# Internet_Of_Everthing.net
KiCad netlist of a schematic drawn in Altium Designer
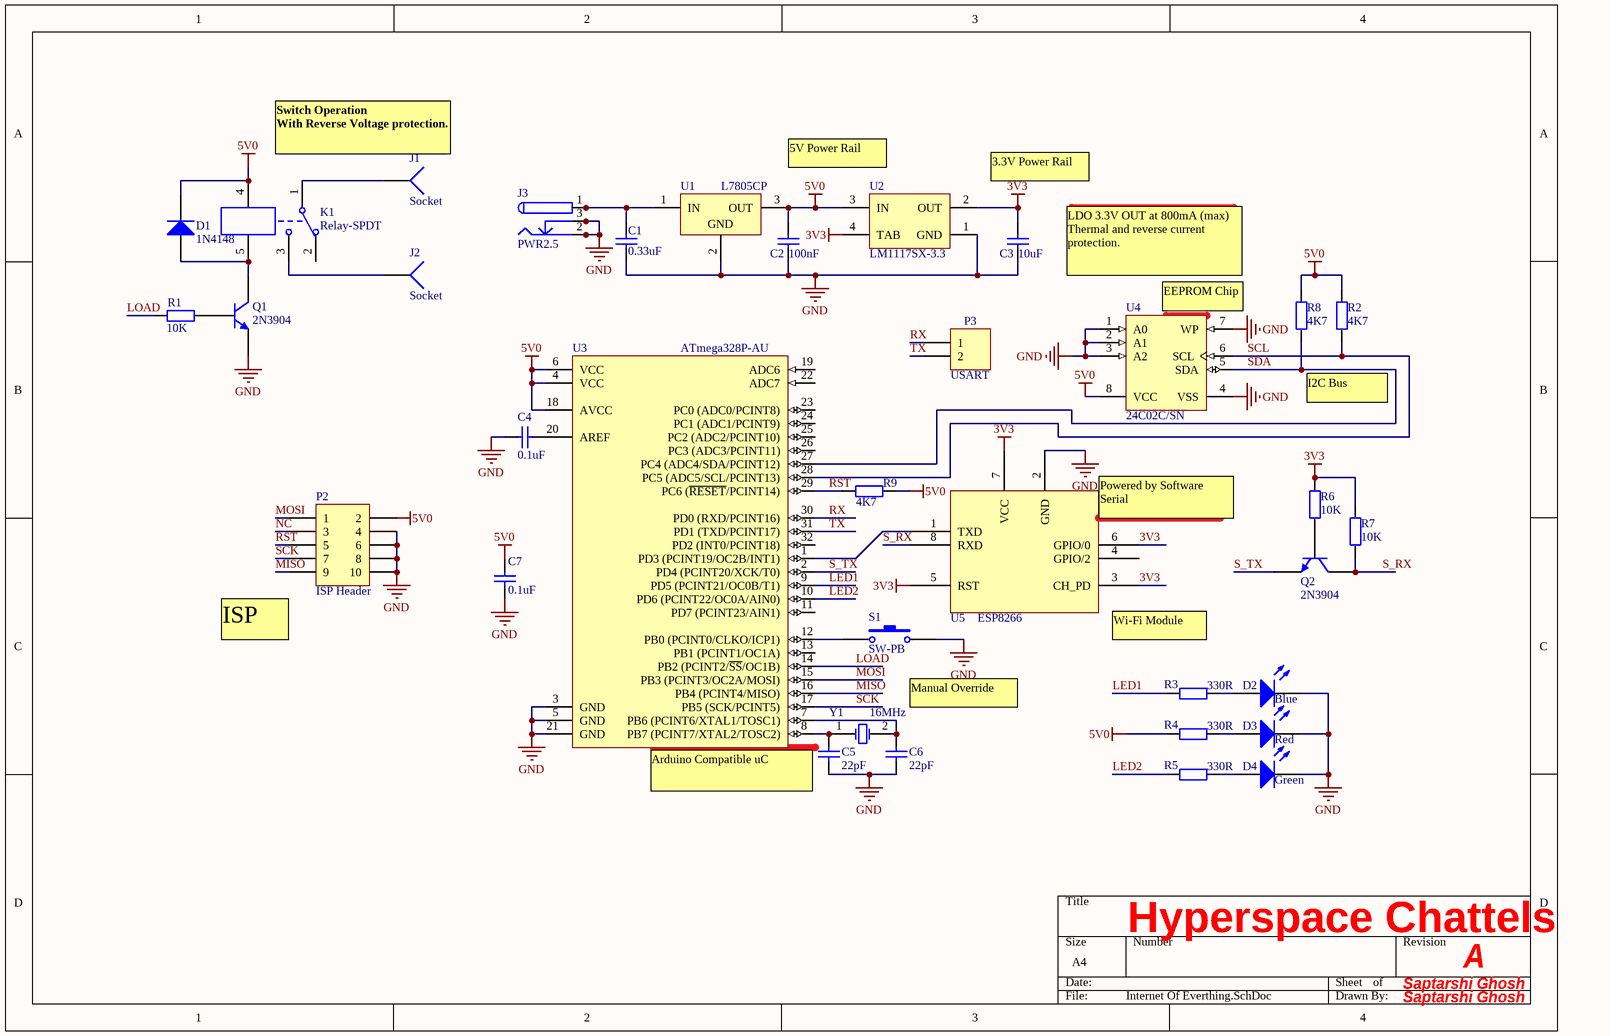
[diagram p0: Internet Of Everthing.SchDoc]

(export (version "E")
  (design (tool "Eeschema 10.0.6"))
  (components
    (comp (ref "C1")
      (value "0.33uF")
      (footprint "6-0805_M")
      (description "Capacitor")
      (fields (field (name "Comment") "Cap") (field (name "PUBLISHER") "Altium Limited"))
      (libsource (lib "Miscellaneous Devices") (part "Cap"))
    )
    (comp (ref "C2")
      (value "100nF")
      (footprint "6-0805_M")
      (description "Capacitor")
      (fields (field (name "Comment") "Cap") (field (name "PUBLISHER") "Altium Limited"))
      (libsource (lib "Miscellaneous Devices") (part "Cap"))
    )
    (comp (ref "C3")
      (value "10uF")
      (footprint "6-0805_M")
      (description "Capacitor")
      (fields (field (name "Comment") "Cap") (field (name "PUBLISHER") "Altium Limited"))
      (libsource (lib "Miscellaneous Devices") (part "Cap"))
    )
    (comp (ref "C4")
      (value "0.1uF")
      (footprint "6-0805_M")
      (description "Capacitor")
      (fields (field (name "Comment") "Cap") (field (name "PUBLISHER") "Altium Limited"))
      (libsource (lib "Miscellaneous Devices") (part "Cap"))
    )
    (comp (ref "C5")
      (value "22pF")
      (footprint "6-0805_M")
      (description "Capacitor")
      (fields (field (name "Comment") "Cap") (field (name "PUBLISHER") "Altium Limited"))
      (libsource (lib "Miscellaneous Devices") (part "Cap"))
    )
    (comp (ref "C6")
      (value "22pF")
      (footprint "6-0805_M")
      (description "Capacitor")
      (fields (field (name "Comment") "Cap") (field (name "PUBLISHER") "Altium Limited"))
      (libsource (lib "Miscellaneous Devices") (part "Cap"))
    )
    (comp (ref "C7")
      (value "0.1uF")
      (footprint "6-0805_M")
      (description "Capacitor")
      (fields (field (name "Comment") "Cap") (field (name "PUBLISHER") "Altium Limited"))
      (libsource (lib "Miscellaneous Devices") (part "Cap"))
    )
    (comp (ref "D1")
      (value "1N4148")
      (footprint "SOD-323")
      (description "High Conductance Fast Diode")
      (fields (field (name "PUBLISHER") "Altium Limited"))
      (libsource (lib "FSC Discrete Diode") (part "1N4148"))
    )
    (comp (ref "D2")
      (value "LED0")
      (footprint "6-0805_M")
      (description "Typical INFRARED GaAs LED")
      (fields (field (name "PUBLISHER") "Altium Limited"))
      (libsource (lib "Miscellaneous Devices") (part "LED0"))
    )
    (comp (ref "D3")
      (value "LED0")
      (footprint "6-0805_M")
      (description "Typical INFRARED GaAs LED")
      (fields (field (name "PUBLISHER") "Altium Limited"))
      (libsource (lib "Miscellaneous Devices") (part "LED0"))
    )
    (comp (ref "D4")
      (value "LED0")
      (footprint "6-0805_M")
      (description "Typical INFRARED GaAs LED")
      (fields (field (name "PUBLISHER") "Altium Limited"))
      (libsource (lib "Miscellaneous Devices") (part "LED0"))
    )
    (comp (ref "J1")
      (value "Socket")
      (footprint "PIN1")
      (fields (field (name "PUBLISHER") "Altium Limited"))
      (libsource (lib "Miscellaneous Connectors") (part "Socket"))
    )
    (comp (ref "J2")
      (value "Socket")
      (footprint "PIN1")
      (fields (field (name "PUBLISHER") "Altium Limited"))
      (libsource (lib "Miscellaneous Connectors") (part "Socket"))
    )
    (comp (ref "J3")
      (value "PWR2.5")
      (footprint "KLD-0202")
      (description "Low Voltage Power Supply Connector")
      (fields (field (name "PUBLISHER") "Altium Limited"))
      (libsource (lib "Miscellaneous Connectors") (part "PWR2.5"))
    )
    (comp (ref "K1")
      (value "Relay-SPDT")
      (footprint "G5LA-141")
      (description "Single-Pole Dual-Throw Relay")
      (fields (field (name "PUBLISHER") "Altium Limited"))
      (libsource (lib "Miscellaneous Devices") (part "Relay-SPDT"))
    )
    (comp (ref "P2")
      (value "ISP Header")
      (footprint "HDR2X5")
      (description "Header, 5-Pin, Dual row")
      (fields (field (name "PUBLISHER") "Altium Limited"))
      (libsource (lib "Miscellaneous Connectors") (part "Header 5X2"))
    )
    (comp (ref "P3")
      (value "USART")
      (footprint "HDR1X2")
      (description "Header, 2-Pin")
      (fields (field (name "PUBLISHER") "Altium Limited"))
      (libsource (lib "Miscellaneous Connectors") (part "Header 2"))
    )
    (comp (ref "Q1")
      (value "2N3904")
      (footprint "SOT-23_M")
      (description "NPN General Purpose Amplifier")
      (fields (field (name "PUBLISHER") "Altium Limited"))
      (libsource (lib "FSC Discrete BJT") (part "2N3904"))
    )
    (comp (ref "Q2")
      (value "2N3904")
      (footprint "SOT-23_M")
      (description "NPN General Purpose Amplifier")
      (fields (field (name "PUBLISHER") "Altium Limited"))
      (libsource (lib "FSC Discrete BJT") (part "2N3904"))
    )
    (comp (ref "R1")
      (value "10K")
      (footprint "6-0805_M")
      (description "Resistor")
      (fields (field (name "Comment") "Res2") (field (name "PUBLISHER") "Altium Limited"))
      (libsource (lib "") (part "Res2_3"))
    )
    (comp (ref "R2")
      (value "4K7")
      (footprint "6-0805_M")
      (description "Resistor")
      (fields (field (name "Comment") "Res2") (field (name "PUBLISHER") "Altium Limited"))
      (libsource (lib "Miscellaneous Devices") (part "Res2"))
    )
    (comp (ref "R3")
      (value "330R")
      (footprint "6-0805_M")
      (description "Resistor")
      (fields (field (name "Comment") "Res2") (field (name "PUBLISHER") "Altium Limited"))
      (libsource (lib "") (part "Res2_2"))
    )
    (comp (ref "R4")
      (value "330R")
      (footprint "6-0805_M")
      (description "Resistor")
      (fields (field (name "Comment") "Res2") (field (name "PUBLISHER") "Altium Limited"))
      (libsource (lib "") (part "Res2_2"))
    )
    (comp (ref "R5")
      (value "330R")
      (footprint "6-0805_M")
      (description "Resistor")
      (fields (field (name "Comment") "Res2") (field (name "PUBLISHER") "Altium Limited"))
      (libsource (lib "") (part "Res2_2"))
    )
    (comp (ref "R6")
      (value "10K")
      (footprint "6-0805_M")
      (description "Resistor")
      (fields (field (name "Comment") "Res2") (field (name "PUBLISHER") "Altium Limited"))
      (libsource (lib "") (part "Res2_1"))
    )
    (comp (ref "R7")
      (value "10K")
      (footprint "6-0805_M")
      (description "Resistor")
      (fields (field (name "Comment") "Res2") (field (name "PUBLISHER") "Altium Limited"))
      (libsource (lib "") (part "Res2_1"))
    )
    (comp (ref "R8")
      (value "4K7")
      (footprint "6-0805_M")
      (description "Resistor")
      (fields (field (name "Comment") "Res2") (field (name "PUBLISHER") "Altium Limited"))
      (libsource (lib "Miscellaneous Devices") (part "Res2"))
    )
    (comp (ref "R9")
      (value "4K7")
      (footprint "6-0805_M")
      (description "Resistor")
      (fields (field (name "Comment") "g") (field (name "PUBLISHER") "Altium Limited"))
      (libsource (lib "") (part "Res2_2"))
    )
    (comp (ref "S1")
      (value "SW-PB")
      (footprint "Tactile Swithc")
      (description "Switch")
      (fields (field (name "PUBLISHER") "Altium Limited"))
      (libsource (lib "Miscellaneous Devices") (part "SW-PB"))
    )
    (comp (ref "U1")
      (value "L7805CP")
      (footprint "SOT223_M")
      (description "Positive Voltage Regulator")
      (fields (field (name "PUBLISHER") "Altium Limited"))
      (libsource (lib "ST Power Mgt Voltage Regulator") (part "L7805CP"))
    )
    (comp (ref "U2")
      (value "LM1117SX-3.3")
      (footprint "SOT223_M")
      (description "800mA Low-Dropout Linear Regulator, 3-pin TO-263")
      (fields
        (field (name "MANUFACTURER") "National Semiconductor")
        (field (name "PUBLISHER") "Altium Limited")
      )
      (libsource (lib "NSC LDO") (part "LM1117SX-3.3"))
    )
    (comp (ref "U3")
      (value "ATmega328P-AU")
      (footprint "32A_M")
      (fields (field (name "PUBLISHER") "Altium Limited"))
      (libsource (lib "Atmel Microcontroller 8-Bit megaAVR") (part "ATmega328P-AU"))
    )
    (comp (ref "U4")
      (value "24C02C/SN")
      (footprint "SOIC-SN8_M")
      (description "2Kbit, 400kHz, 5V, I2C Serial EEPROM, 8-Pin SOIC 150mil, Commercial Temperature")
      (fields (field (name "PUBLISHER") "Altium Limited"))
      (libsource (lib "Microchip Memory I2C Serial EEPROM") (part "24C02C/SN"))
    )
    (comp (ref "U5")
      (value "ESP8266")
      (footprint "HDR2X4")
      (description "Low cost, Wi-Fi module")
      (libsource (lib "MSP430") (part "ESP8266"))
    )
    (comp (ref "Y1")
      (value "16MHz")
      (footprint "RAD-0.2")
      (description "Crystal Oscillator")
      (fields (field (name "PUBLISHER") "Altium Limited"))
      (libsource (lib "Miscellaneous Devices") (part "XTAL"))
    )
  )
  (nets
    (net (code "1") (name "/LED1") (class "Default")
      (node (ref "R3") (pin "2") (pinfunction "2_2") (pintype "passive"))
      (node (ref "U3") (pin "9") (pinfunction "PD5_(PCINT21/OC0B/T1)_9") (pintype "bidirectional"))
    )
    (net (code "2") (name "/LED2") (class "Default")
      (node (ref "R5") (pin "2") (pinfunction "2_2") (pintype "passive"))
      (node (ref "U3") (pin "10") (pinfunction "PD6_(PCINT22/OC0A/AIN0)_10") (pintype "bidirectional"))
    )
    (net (code "3") (name "/LOAD") (class "Default")
      (node (ref "R1") (pin "1") (pinfunction "1_1") (pintype "passive"))
      (node (ref "U3") (pin "14") (pinfunction "PB2_(PCINT2/~{SS}/OC1B)_14") (pintype "bidirectional"))
    )
    (net (code "4") (name "/MISO") (class "Default")
      (node (ref "P2") (pin "9") (pinfunction "9_9") (pintype "passive"))
      (node (ref "U3") (pin "16") (pinfunction "PB4_(PCINT4/MISO)_16") (pintype "bidirectional"))
    )
    (net (code "5") (name "/MOSI") (class "Default")
      (node (ref "P2") (pin "1") (pinfunction "1_1") (pintype "passive"))
      (node (ref "U3") (pin "15") (pinfunction "PB3_(PCINT3/OC2A/MOSI)_15") (pintype "bidirectional"))
    )
    (net (code "6") (name "/NC") (class "Default")
      (node (ref "P2") (pin "3") (pinfunction "3_3") (pintype "passive"))
    )
    (net (code "7") (name "/RST") (class "Default")
      (node (ref "P2") (pin "5") (pinfunction "5_5") (pintype "passive"))
      (node (ref "R9") (pin "2") (pinfunction "2_2") (pintype "passive"))
      (node (ref "U3") (pin "29") (pinfunction "PC6_(~{RESET}/PCINT14)_29") (pintype "bidirectional"))
    )
    (net (code "8") (name "/RX") (class "Default")
      (node (ref "P3") (pin "1") (pinfunction "1_1") (pintype "passive"))
      (node (ref "U3") (pin "30") (pinfunction "PD0_(RXD/PCINT16)_30") (pintype "bidirectional"))
    )
    (net (code "9") (name "/SCK") (class "Default")
      (node (ref "P2") (pin "7") (pinfunction "7_7") (pintype "passive"))
      (node (ref "U3") (pin "17") (pinfunction "PB5_(SCK/PCINT5)_17") (pintype "bidirectional"))
    )
    (net (code "10") (name "/SCL") (class "Default")
      (node (ref "R2") (pin "1") (pinfunction "1_1") (pintype "passive"))
      (node (ref "U3") (pin "28") (pinfunction "PC5_(ADC5/SCL/PCINT13)_28") (pintype "bidirectional"))
      (node (ref "U4") (pin "6") (pinfunction "SCL_6") (pintype "input"))
    )
    (net (code "11") (name "/SDA") (class "Default")
      (node (ref "R8") (pin "1") (pinfunction "1_1") (pintype "passive"))
      (node (ref "U3") (pin "27") (pinfunction "PC4_(ADC4/SDA/PCINT12)_27") (pintype "bidirectional"))
      (node (ref "U4") (pin "5") (pinfunction "SDA_5") (pintype "bidirectional"))
    )
    (net (code "12") (name "/S_RX") (class "Default")
      (node (ref "Q2") (pin "3") (pinfunction "C_3") (pintype "passive"))
      (node (ref "R7") (pin "2") (pinfunction "2_2") (pintype "passive"))
      (node (ref "U5") (pin "8") (pinfunction "RXD_8") (pintype "passive"))
    )
    (net (code "13") (name "/S_TX") (class "Default")
      (node (ref "Q2") (pin "2") (pinfunction "E_2") (pintype "passive"))
      (node (ref "U3") (pin "2") (pinfunction "PD4_(PCINT20/XCK/T0)_2") (pintype "bidirectional"))
    )
    (net (code "14") (name "/TX") (class "Default")
      (node (ref "P3") (pin "2") (pinfunction "2_2") (pintype "passive"))
      (node (ref "U3") (pin "31") (pinfunction "PD1_(TXD/PCINT17)_31") (pintype "bidirectional"))
    )
    (net (code "15") (name "3V3") (class "Default")
      (node (ref "C3") (pin "1") (pinfunction "1_1") (pintype "passive"))
      (node (ref "R6") (pin "1") (pinfunction "1_1") (pintype "passive"))
      (node (ref "R7") (pin "1") (pinfunction "1_1") (pintype "passive"))
      (node (ref "U2") (pin "2") (pinfunction "OUT_2") (pintype "power_in"))
      (node (ref "U2") (pin "4") (pinfunction "TAB_4") (pintype "power_in"))
      (node (ref "U5") (pin "3") (pinfunction "CH_PD_3") (pintype "passive"))
      (node (ref "U5") (pin "5") (pinfunction "RST_5") (pintype "passive"))
      (node (ref "U5") (pin "6") (pinfunction "GPIO/0_6") (pintype "passive"))
      (node (ref "U5") (pin "7") (pinfunction "VCC_7") (pintype "passive"))
    )
    (net (code "16") (name "5V0") (class "Default")
      (node (ref "C2") (pin "1") (pinfunction "1_1") (pintype "passive"))
      (node (ref "C7") (pin "2") (pinfunction "2_2") (pintype "passive"))
      (node (ref "D1") (pin "2") (pinfunction "K_2") (pintype "passive"))
      (node (ref "K1") (pin "4") (pinfunction "4_4") (pintype "passive"))
      (node (ref "P2") (pin "2") (pinfunction "2_2") (pintype "passive"))
      (node (ref "R2") (pin "2") (pinfunction "2_2") (pintype "passive"))
      (node (ref "R4") (pin "2") (pinfunction "2_2") (pintype "passive"))
      (node (ref "R8") (pin "2") (pinfunction "2_2") (pintype "passive"))
      (node (ref "R9") (pin "1") (pinfunction "1_1") (pintype "passive"))
      (node (ref "U1") (pin "3") (pinfunction "OUT_3") (pintype "open_emitter"))
      (node (ref "U2") (pin "3") (pinfunction "IN_3") (pintype "power_in"))
      (node (ref "U3") (pin "18") (pinfunction "AVCC_18") (pintype "power_in"))
      (node (ref "U3") (pin "4") (pinfunction "VCC_4") (pintype "power_in"))
      (node (ref "U3") (pin "6") (pinfunction "VCC_6") (pintype "power_in"))
      (node (ref "U4") (pin "8") (pinfunction "VCC_8") (pintype "power_in"))
    )
    (net (code "17") (name "GND") (class "Default")
      (node (ref "C1") (pin "1") (pinfunction "1_1") (pintype "passive"))
      (node (ref "C2") (pin "2") (pinfunction "2_2") (pintype "passive"))
      (node (ref "C3") (pin "2") (pinfunction "2_2") (pintype "passive"))
      (node (ref "C4") (pin "1") (pinfunction "1_1") (pintype "passive"))
      (node (ref "C5") (pin "2") (pinfunction "2_2") (pintype "passive"))
      (node (ref "C6") (pin "2") (pinfunction "2_2") (pintype "passive"))
      (node (ref "C7") (pin "1") (pinfunction "1_1") (pintype "passive"))
      (node (ref "D2") (pin "2") (pinfunction "K_2") (pintype "passive"))
      (node (ref "D3") (pin "2") (pinfunction "K_2") (pintype "passive"))
      (node (ref "D4") (pin "2") (pinfunction "K_2") (pintype "passive"))
      (node (ref "J3") (pin "2") (pinfunction "2_2") (pintype "power_in"))
      (node (ref "J3") (pin "2A") (pinfunction "2A_2A") (pintype "power_in"))
      (node (ref "J3") (pin "2B") (pinfunction "2B_2B") (pintype "power_in"))
      (node (ref "J3") (pin "3") (pinfunction "3_3") (pintype "power_in"))
      (node (ref "J3") (pin "3A") (pinfunction "3A_3A") (pintype "power_in"))
      (node (ref "J3") (pin "3B") (pinfunction "3B_3B") (pintype "power_in"))
      (node (ref "P2") (pin "10") (pinfunction "10_10") (pintype "passive"))
      (node (ref "P2") (pin "4") (pinfunction "4_4") (pintype "passive"))
      (node (ref "P2") (pin "6") (pinfunction "6_6") (pintype "passive"))
      (node (ref "P2") (pin "8") (pinfunction "8_8") (pintype "passive"))
      (node (ref "Q1") (pin "2") (pinfunction "E_2") (pintype "passive"))
      (node (ref "S1") (pin "2") (pinfunction "2_2") (pintype "passive"))
      (node (ref "U1") (pin "2") (pinfunction "GND_2") (pintype "power_in"))
      (node (ref "U2") (pin "1") (pinfunction "GND_1") (pintype "power_in"))
      (node (ref "U3") (pin "21") (pinfunction "GND_21") (pintype "power_in"))
      (node (ref "U3") (pin "3") (pinfunction "GND_3") (pintype "power_in"))
      (node (ref "U3") (pin "5") (pinfunction "GND_5") (pintype "power_in"))
      (node (ref "U4") (pin "1") (pinfunction "A0_1") (pintype "input"))
      (node (ref "U4") (pin "2") (pinfunction "A1_2") (pintype "input"))
      (node (ref "U4") (pin "3") (pinfunction "A2_3") (pintype "input"))
      (node (ref "U4") (pin "4") (pinfunction "VSS_4") (pintype "power_in"))
      (node (ref "U4") (pin "7") (pinfunction "WP_7") (pintype "input"))
      (node (ref "U5") (pin "2") (pinfunction "GND_2") (pintype "passive"))
    )
    (net (code "18") (name "Net-(D1-A)") (class "Default")
      (node (ref "D1") (pin "1") (pinfunction "A_1") (pintype "passive"))
      (node (ref "K1") (pin "5") (pinfunction "5_5") (pintype "passive"))
      (node (ref "Q1") (pin "3") (pinfunction "C_3") (pintype "passive"))
    )
    (net (code "19") (name "Net-(D2-A)") (class "Default")
      (node (ref "D2") (pin "1") (pinfunction "A_1") (pintype "passive"))
      (node (ref "R3") (pin "1") (pinfunction "1_1") (pintype "passive"))
    )
    (net (code "20") (name "Net-(D3-A)") (class "Default")
      (node (ref "D3") (pin "1") (pinfunction "A_1") (pintype "passive"))
      (node (ref "R4") (pin "1") (pinfunction "1_1") (pintype "passive"))
    )
    (net (code "21") (name "Net-(D4-A)") (class "Default")
      (node (ref "D4") (pin "1") (pinfunction "A_1") (pintype "passive"))
      (node (ref "R5") (pin "1") (pinfunction "1_1") (pintype "passive"))
    )
    (net (code "22") (name "Net-(J1-Pad1)") (class "Default")
      (node (ref "J1") (pin "1") (pinfunction "1_1") (pintype "passive"))
      (node (ref "K1") (pin "1") (pinfunction "1_1") (pintype "passive"))
    )
    (net (code "23") (name "Net-(J2-Pad1)") (class "Default")
      (node (ref "J2") (pin "1") (pinfunction "1_1") (pintype "passive"))
      (node (ref "K1") (pin "3") (pinfunction "3_3") (pintype "passive"))
    )
    (net (code "24") (name "Net-(Q1-B)") (class "Default")
      (node (ref "Q1") (pin "1") (pinfunction "B_1") (pintype "passive"))
      (node (ref "R1") (pin "2") (pinfunction "2_2") (pintype "passive"))
    )
    (net (code "25") (name "Net-(Q2-B)") (class "Default")
      (node (ref "Q2") (pin "1") (pinfunction "B_1") (pintype "passive"))
      (node (ref "R6") (pin "2") (pinfunction "2_2") (pintype "passive"))
    )
    (net (code "26") (name "Net-(U1-IN)") (class "Default")
      (node (ref "C1") (pin "2") (pinfunction "2_2") (pintype "passive"))
      (node (ref "J3") (pin "1") (pinfunction "1_1") (pintype "power_in"))
      (node (ref "J3") (pin "1A") (pinfunction "1A_1A") (pintype "power_in"))
      (node (ref "J3") (pin "1B") (pinfunction "1B_1B") (pintype "power_in"))
      (node (ref "U1") (pin "1") (pinfunction "IN_1") (pintype "power_in"))
    )
    (net (code "27") (name "Net-(U3-AREF)") (class "Default")
      (node (ref "C4") (pin "2") (pinfunction "2_2") (pintype "passive"))
      (node (ref "U3") (pin "20") (pinfunction "AREF_20") (pintype "passive"))
    )
    (net (code "28") (name "Net-(U3-PB0_(PCINT0{slash}CLKO{slash}ICP1))") (class "Default")
      (node (ref "S1") (pin "1") (pinfunction "1_1") (pintype "passive"))
      (node (ref "U3") (pin "12") (pinfunction "PB0_(PCINT0/CLKO/ICP1)_12") (pintype "bidirectional"))
    )
    (net (code "29") (name "Net-(U3-PB6_(PCINT6{slash}XTAL1{slash}TOSC1))") (class "Default")
      (node (ref "C6") (pin "1") (pinfunction "1_1") (pintype "passive"))
      (node (ref "U3") (pin "7") (pinfunction "PB6_(PCINT6/XTAL1/TOSC1)_7") (pintype "bidirectional"))
      (node (ref "Y1") (pin "2") (pinfunction "OSC2_2") (pintype "passive"))
    )
    (net (code "30") (name "Net-(U3-PB7_(PCINT7{slash}XTAL2{slash}TOSC2))") (class "Default")
      (node (ref "C5") (pin "1") (pinfunction "1_1") (pintype "passive"))
      (node (ref "U3") (pin "8") (pinfunction "PB7_(PCINT7/XTAL2/TOSC2)_8") (pintype "bidirectional"))
      (node (ref "Y1") (pin "1") (pinfunction "OSC1_1") (pintype "passive"))
    )
    (net (code "31") (name "Net-(U3-PD3_(PCINT19{slash}OC2B{slash}INT1))") (class "Default")
      (node (ref "U3") (pin "1") (pinfunction "PD3_(PCINT19/OC2B/INT1)_1") (pintype "bidirectional"))
      (node (ref "U5") (pin "1") (pinfunction "TXD_1") (pintype "passive"))
    )
    (net (code "32") (name "unconnected-(K1-Pad2)") (class "Default")
      (node (ref "K1") (pin "2") (pinfunction "2_2") (pintype "passive"))
    )
    (net (code "33") (name "unconnected-(U3-ADC6-Pad19)") (class "Default")
      (node (ref "U3") (pin "19") (pinfunction "ADC6_19") (pintype "input"))
    )
    (net (code "34") (name "unconnected-(U3-ADC7-Pad22)") (class "Default")
      (node (ref "U3") (pin "22") (pinfunction "ADC7_22") (pintype "input"))
    )
    (net (code "35") (name "unconnected-(U3-PB1_(PCINT1{slash}OC1A)-Pad13)") (class "Default")
      (node (ref "U3") (pin "13") (pinfunction "PB1_(PCINT1/OC1A)_13") (pintype "bidirectional"))
    )
    (net (code "36") (name "unconnected-(U3-PC0_(ADC0{slash}PCINT8)-Pad23)") (class "Default")
      (node (ref "U3") (pin "23") (pinfunction "PC0_(ADC0/PCINT8)_23") (pintype "bidirectional"))
    )
    (net (code "37") (name "unconnected-(U3-PC1_(ADC1{slash}PCINT9)-Pad24)") (class "Default")
      (node (ref "U3") (pin "24") (pinfunction "PC1_(ADC1/PCINT9)_24") (pintype "bidirectional"))
    )
    (net (code "38") (name "unconnected-(U3-PC2_(ADC2{slash}PCINT10)-Pad25)") (class "Default")
      (node (ref "U3") (pin "25") (pinfunction "PC2_(ADC2/PCINT10)_25") (pintype "bidirectional"))
    )
    (net (code "39") (name "unconnected-(U3-PC3_(ADC3{slash}PCINT11)-Pad26)") (class "Default")
      (node (ref "U3") (pin "26") (pinfunction "PC3_(ADC3/PCINT11)_26") (pintype "bidirectional"))
    )
    (net (code "40") (name "unconnected-(U3-PD2_(INT0{slash}PCINT18)-Pad32)") (class "Default")
      (node (ref "U3") (pin "32") (pinfunction "PD2_(INT0/PCINT18)_32") (pintype "bidirectional"))
    )
    (net (code "41") (name "unconnected-(U3-PD7_(PCINT23{slash}AIN1)-Pad11)") (class "Default")
      (node (ref "U3") (pin "11") (pinfunction "PD7_(PCINT23/AIN1)_11") (pintype "bidirectional"))
    )
    (net (code "42") (name "unconnected-(U5-GPIO{slash}2-Pad4)") (class "Default")
      (node (ref "U5") (pin "4") (pinfunction "GPIO/2_4") (pintype "passive"))
    )
  )
)
